# ToolSub.net
KiCad netlist of a schematic drawn in Altium Designer
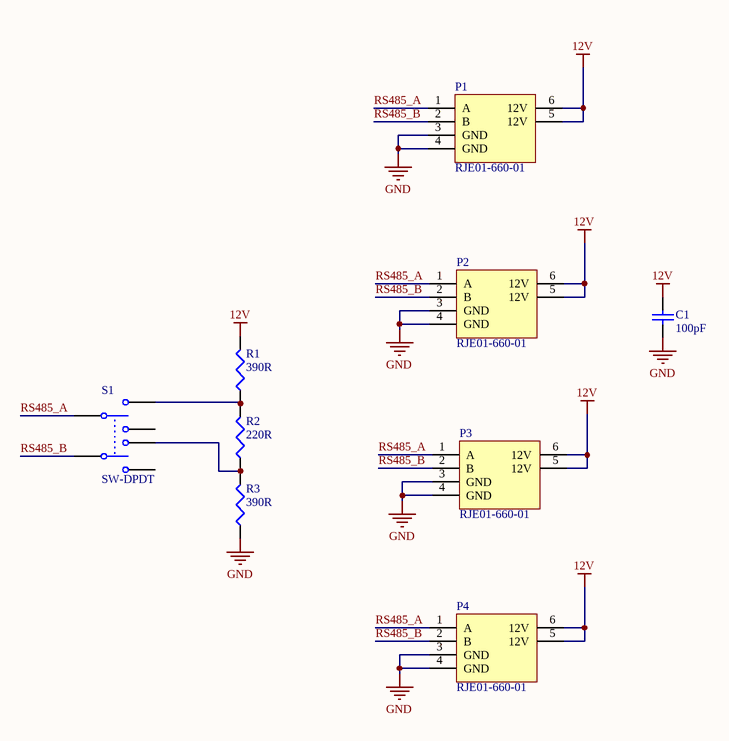
[diagram p0: ToolSub.SchDoc]

(export (version "E")
  (design (tool "Eeschema 10.0.6"))
  (components
    (comp (ref "C1")
      (value "100pF")
      (footprint "C1206")
      (description "Capacitor (Semiconductor SIM Model)")
      (fields (field (name "PUBLISHER") "Altium Limited"))
      (libsource (lib "ToolDoorController") (part "Cap 100pF"))
    )
    (comp (ref "P1")
      (value "RJE01-660-01")
      (footprint "RJ11")
      (description "RJ11")
      (libsource (lib "ToolDoorController") (part "RJ11"))
    )
    (comp (ref "P2")
      (value "RJE01-660-01")
      (footprint "RJ11")
      (description "RJ11")
      (libsource (lib "ToolDoorController") (part "RJ11"))
    )
    (comp (ref "P3")
      (value "RJE01-660-01")
      (footprint "RJ11")
      (description "RJ11")
      (libsource (lib "ToolDoorController") (part "RJ11"))
    )
    (comp (ref "P4")
      (value "RJE01-660-01")
      (footprint "RJ11")
      (description "RJ11")
      (libsource (lib "ToolDoorController") (part "RJ11"))
    )
    (comp (ref "R1")
      (value "390R")
      (footprint "C1206")
      (description "Resistor")
      (fields (field (name "PUBLISHER") "Altium Limited"))
      (libsource (lib "ToolDoorController") (part "Resistor-390R"))
    )
    (comp (ref "R2")
      (value "220R")
      (footprint "C1206")
      (description "Resistor")
      (fields (field (name "PUBLISHER") "Altium Limited"))
      (libsource (lib "ToolDoorController") (part "Resistor-220R"))
    )
    (comp (ref "R3")
      (value "390R")
      (footprint "C1206")
      (description "Resistor")
      (fields (field (name "PUBLISHER") "Altium Limited"))
      (libsource (lib "ToolDoorController") (part "Resistor-390R"))
    )
    (comp (ref "S1")
      (value "SW-DPDT")
      (footprint "DPDT-6")
      (description "Double-Pole, Double-Throw Switch")
      (fields (field (name "PUBLISHER") "Altium Limited"))
      (libsource (lib "ToolSub") (part "SW-DPDT"))
    )
  )
  (nets
    (net (code "1") (name "/RS485_A") (class "Default")
      (node (ref "P1") (pin "1") (pinfunction "A_1") (pintype "passive"))
      (node (ref "P2") (pin "1") (pinfunction "A_1") (pintype "passive"))
      (node (ref "P3") (pin "1") (pinfunction "A_1") (pintype "passive"))
      (node (ref "P4") (pin "1") (pinfunction "A_1") (pintype "passive"))
      (node (ref "S1") (pin "2") (pinfunction "2_2") (pintype "passive"))
    )
    (net (code "2") (name "/RS485_B") (class "Default")
      (node (ref "P1") (pin "2") (pinfunction "B_2") (pintype "passive"))
      (node (ref "P2") (pin "2") (pinfunction "B_2") (pintype "passive"))
      (node (ref "P3") (pin "2") (pinfunction "B_2") (pintype "passive"))
      (node (ref "P4") (pin "2") (pinfunction "B_2") (pintype "passive"))
      (node (ref "S1") (pin "5") (pinfunction "5_5") (pintype "passive"))
    )
    (net (code "3") (name "12V") (class "Default")
      (node (ref "C1") (pin "2") (pinfunction "2_2") (pintype "passive"))
      (node (ref "P1") (pin "5") (pinfunction "12V_5") (pintype "passive"))
      (node (ref "P1") (pin "6") (pinfunction "12V_6") (pintype "passive"))
      (node (ref "P2") (pin "5") (pinfunction "12V_5") (pintype "passive"))
      (node (ref "P2") (pin "6") (pinfunction "12V_6") (pintype "passive"))
      (node (ref "P3") (pin "5") (pinfunction "12V_5") (pintype "passive"))
      (node (ref "P3") (pin "6") (pinfunction "12V_6") (pintype "passive"))
      (node (ref "P4") (pin "5") (pinfunction "12V_5") (pintype "passive"))
      (node (ref "P4") (pin "6") (pinfunction "12V_6") (pintype "passive"))
      (node (ref "R1") (pin "2") (pinfunction "2_2") (pintype "passive"))
    )
    (net (code "4") (name "GND") (class "Default")
      (node (ref "C1") (pin "1") (pinfunction "1_1") (pintype "passive"))
      (node (ref "P1") (pin "3") (pinfunction "GND_3") (pintype "passive"))
      (node (ref "P1") (pin "4") (pinfunction "GND_4") (pintype "passive"))
      (node (ref "P2") (pin "3") (pinfunction "GND_3") (pintype "passive"))
      (node (ref "P2") (pin "4") (pinfunction "GND_4") (pintype "passive"))
      (node (ref "P3") (pin "3") (pinfunction "GND_3") (pintype "passive"))
      (node (ref "P3") (pin "4") (pinfunction "GND_4") (pintype "passive"))
      (node (ref "P4") (pin "3") (pinfunction "GND_3") (pintype "passive"))
      (node (ref "P4") (pin "4") (pinfunction "GND_4") (pintype "passive"))
      (node (ref "R3") (pin "1") (pinfunction "1_1") (pintype "passive"))
    )
    (net (code "5") (name "Net-(R1-Pad1)") (class "Default")
      (node (ref "R1") (pin "1") (pinfunction "1_1") (pintype "passive"))
      (node (ref "R2") (pin "2") (pinfunction "2_2") (pintype "passive"))
      (node (ref "S1") (pin "1") (pinfunction "1_1") (pintype "passive"))
    )
    (net (code "6") (name "Net-(R2-Pad1)") (class "Default")
      (node (ref "R2") (pin "1") (pinfunction "1_1") (pintype "passive"))
      (node (ref "R3") (pin "2") (pinfunction "2_2") (pintype "passive"))
      (node (ref "S1") (pin "6") (pinfunction "6_6") (pintype "passive"))
    )
    (net (code "7") (name "unconnected-(S1-Pad3)") (class "Default")
      (node (ref "S1") (pin "3") (pinfunction "3_3") (pintype "passive"))
    )
    (net (code "8") (name "unconnected-(S1-Pad4)") (class "Default")
      (node (ref "S1") (pin "4") (pinfunction "4_4") (pintype "passive"))
    )
  )
)
